# si446x-dev.net
KiCad netlist of a schematic drawn in EAGLE
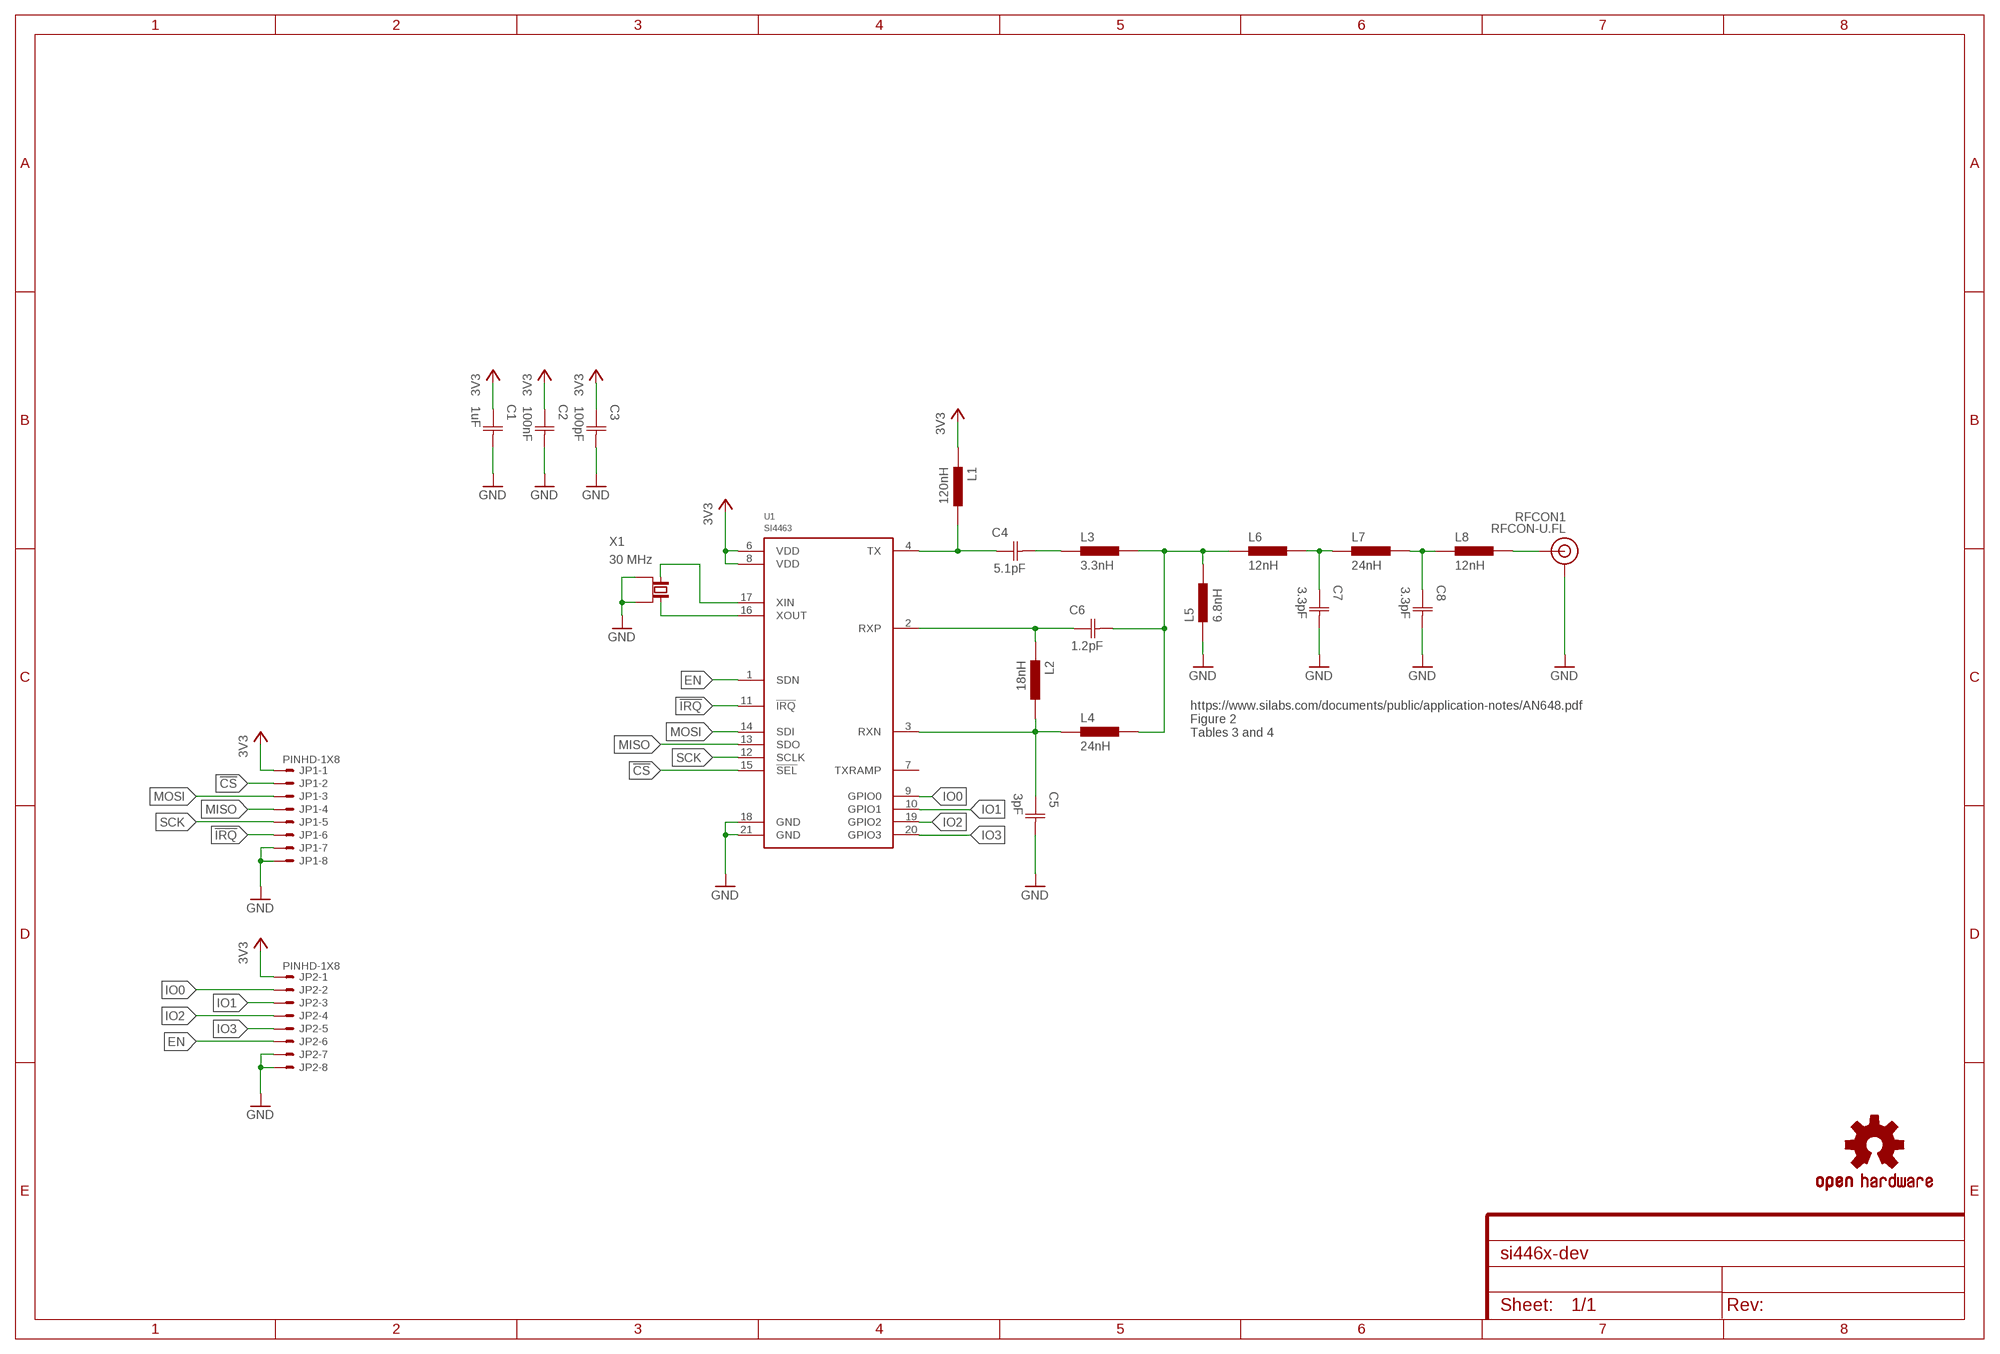
[diagram p0: schematic, sheet 1]

(export (version "E")
  (design (tool "Eeschema 10.0.6"))
  (components
    (comp (ref "C1")
      (value "1uF")
      (footprint "eagle-import:CAP0603")
      (libsource (lib "eagle-import") (part "CAPACITOR-0603"))
    )
    (comp (ref "C2")
      (value "100nF")
      (footprint "eagle-import:CAP0603")
      (libsource (lib "eagle-import") (part "CAPACITOR-0603"))
    )
    (comp (ref "C3")
      (value "100pF")
      (footprint "eagle-import:CAP0603")
      (libsource (lib "eagle-import") (part "CAPACITOR-0603"))
    )
    (comp (ref "C4")
      (value "5.1pF")
      (footprint "eagle-import:CAP0603")
      (libsource (lib "eagle-import") (part "CAPACITOR-0603"))
    )
    (comp (ref "C5")
      (value "3pF")
      (footprint "eagle-import:CAP0603")
      (libsource (lib "eagle-import") (part "CAPACITOR-0603"))
    )
    (comp (ref "C6")
      (value "1.2pF")
      (footprint "eagle-import:CAP0603")
      (libsource (lib "eagle-import") (part "CAPACITOR-0603"))
    )
    (comp (ref "C7")
      (value "3.3pF")
      (footprint "eagle-import:CAP0603")
      (libsource (lib "eagle-import") (part "CAPACITOR-0603"))
    )
    (comp (ref "C8")
      (value "3.3pF")
      (footprint "eagle-import:CAP0603")
      (libsource (lib "eagle-import") (part "CAPACITOR-0603"))
    )
    (comp (ref "JP1")
      (value "PINHD-1X8")
      (footprint "eagle-import:1X08")
      (libsource (lib "eagle-import") (part "PINHD-1X8"))
    )
    (comp (ref "JP2")
      (value "PINHD-1X8")
      (footprint "eagle-import:1X08")
      (libsource (lib "eagle-import") (part "PINHD-1X8"))
    )
    (comp (ref "L1")
      (value "120nH")
      (footprint "eagle-import:IND0603")
      (libsource (lib "eagle-import") (part "INDUCTOR-0603"))
    )
    (comp (ref "L2")
      (value "18nH")
      (footprint "eagle-import:IND0603")
      (libsource (lib "eagle-import") (part "INDUCTOR-0603"))
    )
    (comp (ref "L3")
      (value "3.3nH")
      (footprint "eagle-import:IND0603")
      (libsource (lib "eagle-import") (part "INDUCTOR-0603"))
    )
    (comp (ref "L4")
      (value "24nH")
      (footprint "eagle-import:IND0603")
      (libsource (lib "eagle-import") (part "INDUCTOR-0603"))
    )
    (comp (ref "L5")
      (value "6.8nH")
      (footprint "eagle-import:IND0603")
      (libsource (lib "eagle-import") (part "INDUCTOR-0603"))
    )
    (comp (ref "L6")
      (value "12nH")
      (footprint "eagle-import:IND0603")
      (libsource (lib "eagle-import") (part "INDUCTOR-0603"))
    )
    (comp (ref "L7")
      (value "24nH")
      (footprint "eagle-import:IND0603")
      (libsource (lib "eagle-import") (part "INDUCTOR-0603"))
    )
    (comp (ref "L8")
      (value "12nH")
      (footprint "eagle-import:IND0603")
      (libsource (lib "eagle-import") (part "INDUCTOR-0603"))
    )
    (comp (ref "LOGO1")
      (value "OSHW-LOGOM")
      (footprint "eagle-import:OSHW-LOGO-M")
      (libsource (lib "eagle-import") (part "OSHW-LOGOM"))
    )
    (comp (ref "RFCON1")
      (value "RFCON-U.FL")
      (footprint "eagle-import:U.FL")
      (libsource (lib "eagle-import") (part "RFCON-U.FL"))
    )
    (comp (ref "U1")
      (value "SI4463")
      (footprint "eagle-import:QFN20")
      (libsource (lib "eagle-import") (part "SI4463"))
    )
    (comp (ref "X1")
      (value "30 MHz")
      (footprint "eagle-import:4-SMD-3225")
      (libsource (lib "eagle-import") (part "CRYSTAL_4P"))
    )
  )
  (nets
    (net (code "1") (name "/~{CS}") (class "Default")
      (node (ref "JP1") (pin "2") (pinfunction "S_2") (pintype "passive"))
      (node (ref "U1") (pin "15") (pinfunction "~{SEL}_15") (pintype "bidirectional"))
    )
    (net (code "2") (name "/~{IRQ}") (class "Default")
      (node (ref "JP1") (pin "6") (pinfunction "S_6") (pintype "passive"))
      (node (ref "U1") (pin "11") (pinfunction "~{IRQ}_11") (pintype "bidirectional"))
    )
    (net (code "3") (name "3V3") (class "Default")
      (node (ref "C1") (pin "1") (pinfunction "C1_1") (pintype "passive"))
      (node (ref "C2") (pin "1") (pinfunction "C1_1") (pintype "passive"))
      (node (ref "C3") (pin "1") (pinfunction "C1_1") (pintype "passive"))
      (node (ref "JP1") (pin "1") (pinfunction "S_1") (pintype "passive"))
      (node (ref "JP2") (pin "1") (pinfunction "S_1") (pintype "passive"))
      (node (ref "L1") (pin "1") (pinfunction "1_1") (pintype "passive"))
      (node (ref "U1") (pin "6") (pinfunction "VDD_6") (pintype "bidirectional"))
      (node (ref "U1") (pin "8") (pinfunction "VDD_8") (pintype "bidirectional"))
    )
    (net (code "4") (name "EN") (class "Default")
      (node (ref "JP2") (pin "6") (pinfunction "S_6") (pintype "passive"))
      (node (ref "U1") (pin "1") (pinfunction "SDN_1") (pintype "bidirectional"))
    )
    (net (code "5") (name "GND") (class "Default")
      (node (ref "C1") (pin "2") (pinfunction "C2_2") (pintype "passive"))
      (node (ref "C2") (pin "2") (pinfunction "C2_2") (pintype "passive"))
      (node (ref "C3") (pin "2") (pinfunction "C2_2") (pintype "passive"))
      (node (ref "C5") (pin "2") (pinfunction "C2_2") (pintype "passive"))
      (node (ref "C7") (pin "2") (pinfunction "C2_2") (pintype "passive"))
      (node (ref "C8") (pin "2") (pinfunction "C2_2") (pintype "passive"))
      (node (ref "JP1") (pin "7") (pinfunction "S_7") (pintype "passive"))
      (node (ref "JP1") (pin "8") (pinfunction "S_8") (pintype "passive"))
      (node (ref "JP2") (pin "7") (pinfunction "S_7") (pintype "passive"))
      (node (ref "JP2") (pin "8") (pinfunction "S_8") (pintype "passive"))
      (node (ref "L5") (pin "1") (pinfunction "1_1") (pintype "passive"))
      (node (ref "RFCON1") (pin "P$1") (pinfunction "GND_P$1") (pintype "bidirectional"))
      (node (ref "RFCON1") (pin "P$2") (pinfunction "GND_P$2") (pintype "bidirectional"))
      (node (ref "U1") (pin "18") (pinfunction "GND_18") (pintype "bidirectional"))
      (node (ref "U1") (pin "21") (pinfunction "GND_21") (pintype "bidirectional"))
      (node (ref "X1") (pin "2") (pinfunction "GND_2") (pintype "passive"))
      (node (ref "X1") (pin "4") (pinfunction "GND_4") (pintype "passive"))
    )
    (net (code "6") (name "IO0") (class "Default")
      (node (ref "JP2") (pin "2") (pinfunction "S_2") (pintype "passive"))
      (node (ref "U1") (pin "9") (pinfunction "GPIO0_9") (pintype "bidirectional"))
    )
    (net (code "7") (name "IO1") (class "Default")
      (node (ref "JP2") (pin "3") (pinfunction "S_3") (pintype "passive"))
      (node (ref "U1") (pin "10") (pinfunction "GPIO1_10") (pintype "bidirectional"))
    )
    (net (code "8") (name "IO2") (class "Default")
      (node (ref "JP2") (pin "4") (pinfunction "S_4") (pintype "passive"))
      (node (ref "U1") (pin "19") (pinfunction "GPIO2_19") (pintype "bidirectional"))
    )
    (net (code "9") (name "IO3") (class "Default")
      (node (ref "JP2") (pin "5") (pinfunction "S_5") (pintype "passive"))
      (node (ref "U1") (pin "20") (pinfunction "GPIO3_20") (pintype "bidirectional"))
    )
    (net (code "10") (name "MISO") (class "Default")
      (node (ref "JP1") (pin "4") (pinfunction "S_4") (pintype "passive"))
      (node (ref "U1") (pin "13") (pinfunction "SDO_13") (pintype "bidirectional"))
    )
    (net (code "11") (name "MOSI") (class "Default")
      (node (ref "JP1") (pin "3") (pinfunction "S_3") (pintype "passive"))
      (node (ref "U1") (pin "14") (pinfunction "SDI_14") (pintype "bidirectional"))
    )
    (net (code "12") (name "Net-(C4-C1)") (class "Default")
      (node (ref "C4") (pin "1") (pinfunction "C1_1") (pintype "passive"))
      (node (ref "L1") (pin "2") (pinfunction "2_2") (pintype "passive"))
      (node (ref "U1") (pin "4") (pinfunction "TX_4") (pintype "bidirectional"))
    )
    (net (code "13") (name "Net-(C4-C2)") (class "Default")
      (node (ref "C4") (pin "2") (pinfunction "C2_2") (pintype "passive"))
      (node (ref "L3") (pin "1") (pinfunction "1_1") (pintype "passive"))
    )
    (net (code "14") (name "Net-(C5-C1)") (class "Default")
      (node (ref "C5") (pin "1") (pinfunction "C1_1") (pintype "passive"))
      (node (ref "L2") (pin "2") (pinfunction "2_2") (pintype "passive"))
      (node (ref "L4") (pin "1") (pinfunction "1_1") (pintype "passive"))
      (node (ref "U1") (pin "3") (pinfunction "RXN_3") (pintype "bidirectional"))
    )
    (net (code "15") (name "Net-(C6-C1)") (class "Default")
      (node (ref "C6") (pin "1") (pinfunction "C1_1") (pintype "passive"))
      (node (ref "L2") (pin "1") (pinfunction "1_1") (pintype "passive"))
      (node (ref "U1") (pin "2") (pinfunction "RXP_2") (pintype "bidirectional"))
    )
    (net (code "16") (name "Net-(C6-C2)") (class "Default")
      (node (ref "C6") (pin "2") (pinfunction "C2_2") (pintype "passive"))
      (node (ref "L3") (pin "2") (pinfunction "2_2") (pintype "passive"))
      (node (ref "L4") (pin "2") (pinfunction "2_2") (pintype "passive"))
      (node (ref "L5") (pin "2") (pinfunction "2_2") (pintype "passive"))
      (node (ref "L6") (pin "1") (pinfunction "1_1") (pintype "passive"))
    )
    (net (code "17") (name "Net-(C7-C1)") (class "Default")
      (node (ref "C7") (pin "1") (pinfunction "C1_1") (pintype "passive"))
      (node (ref "L6") (pin "2") (pinfunction "2_2") (pintype "passive"))
      (node (ref "L7") (pin "1") (pinfunction "1_1") (pintype "passive"))
    )
    (net (code "18") (name "Net-(C8-C1)") (class "Default")
      (node (ref "C8") (pin "1") (pinfunction "C1_1") (pintype "passive"))
      (node (ref "L7") (pin "2") (pinfunction "2_2") (pintype "passive"))
      (node (ref "L8") (pin "1") (pinfunction "1_1") (pintype "passive"))
    )
    (net (code "19") (name "Net-(RFCON1-SIGNAL)") (class "Default")
      (node (ref "L8") (pin "2") (pinfunction "2_2") (pintype "passive"))
      (node (ref "RFCON1") (pin "P$3") (pinfunction "SIGNAL_P$3") (pintype "bidirectional"))
    )
    (net (code "20") (name "Net-(U1-XIN)") (class "Default")
      (node (ref "U1") (pin "17") (pinfunction "XIN_17") (pintype "bidirectional"))
      (node (ref "X1") (pin "1") (pinfunction "1_1") (pintype "passive"))
    )
    (net (code "21") (name "Net-(U1-XOUT)") (class "Default")
      (node (ref "U1") (pin "16") (pinfunction "XOUT_16") (pintype "bidirectional"))
      (node (ref "X1") (pin "3") (pinfunction "2_3") (pintype "passive"))
    )
    (net (code "22") (name "SCK") (class "Default")
      (node (ref "JP1") (pin "5") (pinfunction "S_5") (pintype "passive"))
      (node (ref "U1") (pin "12") (pinfunction "SCLK_12") (pintype "bidirectional"))
    )
    (net (code "23") (name "unconnected-(U1-TXRAMP-Pad7)") (class "Default")
      (node (ref "U1") (pin "7") (pinfunction "TXRAMP_7") (pintype "bidirectional"))
    )
  )
)
